# Power_Distribution.net
KiCad netlist of a schematic drawn in Altium Designer
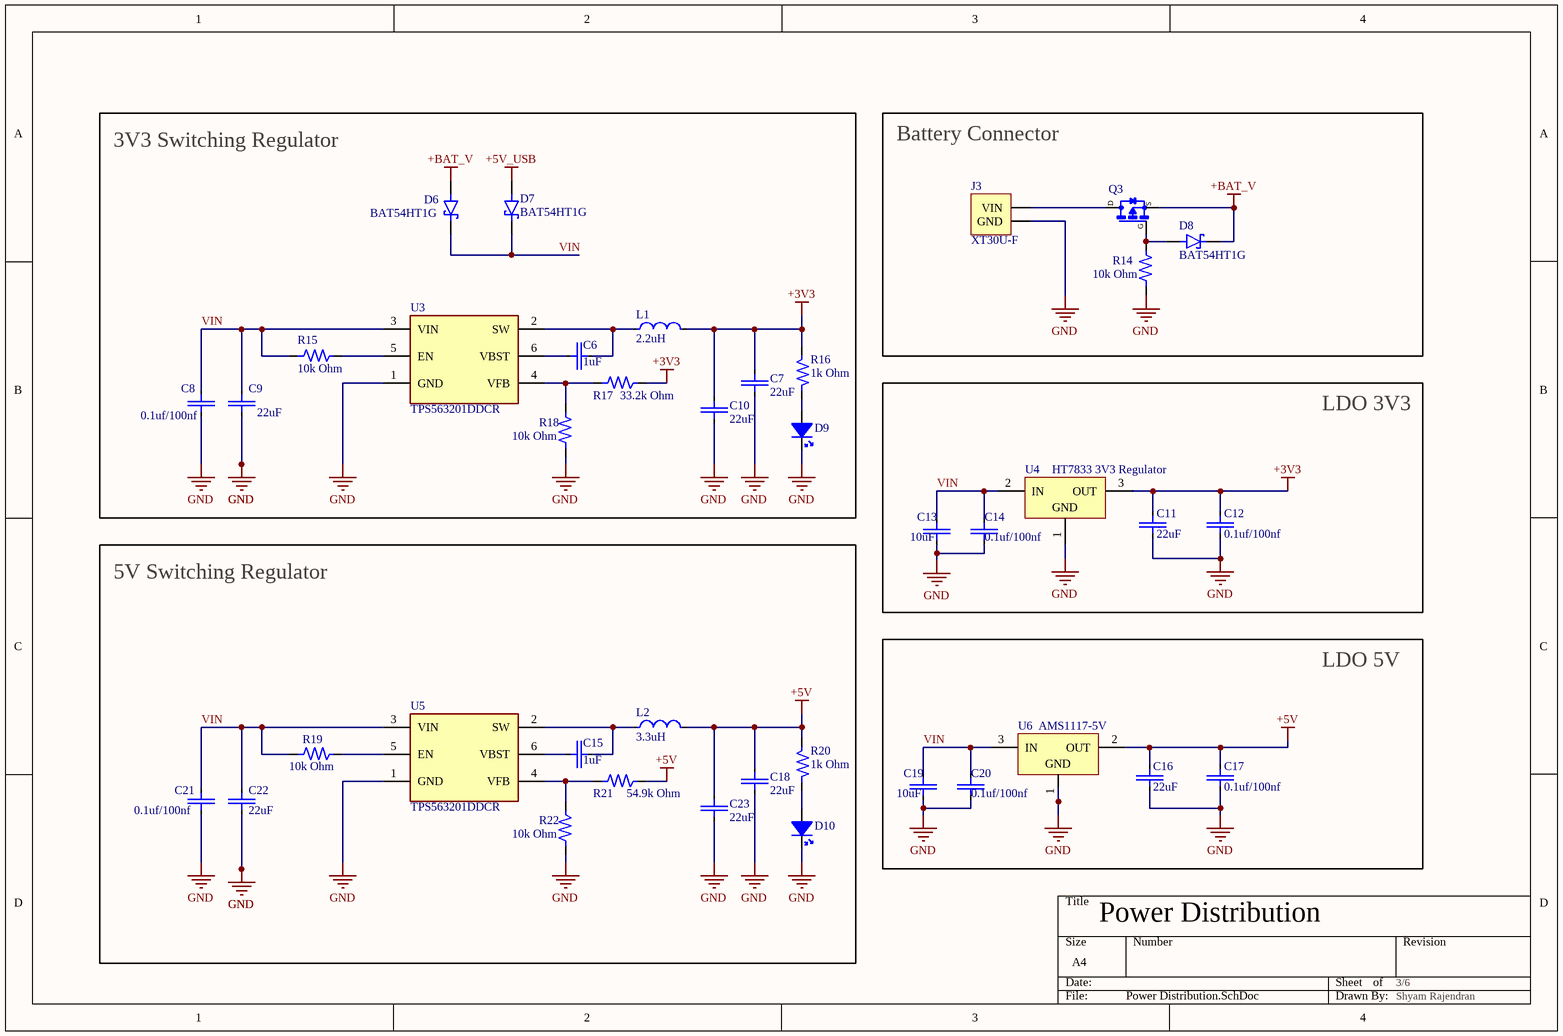
[diagram p0: Power Distribution.SchDoc]

(export (version "E")
  (design (tool "Eeschema 10.0.6"))
  (components
    (comp (ref "C6")
      (value "1uF")
      (footprint "10uf Capacitor")
      (fields
        (field (name "MANUFACTURER") "Yageo")
        (field (name "MANUFACTURER PART NUMBER") "CC0805KKX7R6BB105")
      )
      (libsource (lib "Sirius") (part "CC0805KKX7R6BB105"))
    )
    (comp (ref "C7")
      (value "22uF")
      (footprint "10uf Capacitor")
      (description "CL21A226KOQNNNE-Samsang-16V 22uF X5R ±10% 0805 Multilayer Ceramic Capacitors MLCC – SMD/SMT ROHS")
      (libsource (lib "Sirius") (part "22uF Capacitor"))
    )
    (comp (ref "C8")
      (value "0.1uf/100nf")
      (footprint "0.1uF Capacitor")
      (description "0.1 uF, Multilayer Ceramic Capacitor, 50 V, ï¿½ 10%, X7R, 0805 [2012 Metric]")
      (fields
        (field (name "MANUFACTURER") "Yageo")
        (field (name "MANUFACTURER PART NUMBER") "CC0805KRX7R9BB104")
      )
      (libsource (lib "Sirius") (part "CC0805KRX7R9BB104"))
    )
    (comp (ref "C9")
      (value "22uF")
      (footprint "10uf Capacitor")
      (description "CL21A226KOQNNNE-Samsang-16V 22uF X5R ±10% 0805 Multilayer Ceramic Capacitors MLCC – SMD/SMT ROHS")
      (libsource (lib "Sirius") (part "22uF Capacitor"))
    )
    (comp (ref "C10")
      (value "22uF")
      (footprint "10uf Capacitor")
      (description "CL21A226KOQNNNE-Samsang-16V 22uF X5R ±10% 0805 Multilayer Ceramic Capacitors MLCC – SMD/SMT ROHS")
      (libsource (lib "Sirius") (part "22uF Capacitor"))
    )
    (comp (ref "C11")
      (value "22uF")
      (footprint "10uf Capacitor")
      (description "CL21A226KOQNNNE-Samsang-16V 22uF X5R ±10% 0805 Multilayer Ceramic Capacitors MLCC – SMD/SMT ROHS")
      (libsource (lib "Sirius") (part "22uF Capacitor"))
    )
    (comp (ref "C12")
      (value "0.1uf/100nf")
      (footprint "0.1uF Capacitor")
      (description "0.1 uF, Multilayer Ceramic Capacitor, 50 V, ï¿½ 10%, X7R, 0805 [2012 Metric]")
      (fields
        (field (name "MANUFACTURER") "Yageo")
        (field (name "MANUFACTURER PART NUMBER") "CC0805KRX7R9BB104")
      )
      (libsource (lib "Sirius") (part "CC0805KRX7R9BB104"))
    )
    (comp (ref "C13")
      (value "10uF")
      (footprint "10uf Capacitor")
      (description "10uF, Multilayer Ceramic Capacitor, 25 V, ï¿½ 10%, X5R, 0805 [2012 Metric]")
      (fields
        (field (name "MANUFACTURER") "Murata")
        (field (name "MANUFACTURER PART NUMBER") "GRM21BR61E106KA73L")
      )
      (libsource (lib "Sirius") (part "GRM21BR61E106KA73L"))
    )
    (comp (ref "C14")
      (value "0.1uf/100nf")
      (footprint "0.1uF Capacitor")
      (description "0.1 uF, Multilayer Ceramic Capacitor, 50 V, ï¿½ 10%, X7R, 0805 [2012 Metric]")
      (fields
        (field (name "MANUFACTURER") "Yageo")
        (field (name "MANUFACTURER PART NUMBER") "CC0805KRX7R9BB104")
      )
      (libsource (lib "Sirius") (part "CC0805KRX7R9BB104"))
    )
    (comp (ref "C15")
      (value "1uF")
      (footprint "10uf Capacitor")
      (fields
        (field (name "MANUFACTURER") "Yageo")
        (field (name "MANUFACTURER PART NUMBER") "CC0805KKX7R6BB105")
      )
      (libsource (lib "Sirius") (part "CC0805KKX7R6BB105"))
    )
    (comp (ref "C16")
      (value "22uF")
      (footprint "10uf Capacitor")
      (description "CL21A226KOQNNNE-Samsang-16V 22uF X5R ±10% 0805 Multilayer Ceramic Capacitors MLCC – SMD/SMT ROHS")
      (libsource (lib "Sirius") (part "22uF Capacitor"))
    )
    (comp (ref "C17")
      (value "0.1uf/100nf")
      (footprint "0.1uF Capacitor")
      (description "0.1 uF, Multilayer Ceramic Capacitor, 50 V, ï¿½ 10%, X7R, 0805 [2012 Metric]")
      (fields
        (field (name "MANUFACTURER") "Yageo")
        (field (name "MANUFACTURER PART NUMBER") "CC0805KRX7R9BB104")
      )
      (libsource (lib "Sirius") (part "CC0805KRX7R9BB104"))
    )
    (comp (ref "C18")
      (value "22uF")
      (footprint "10uf Capacitor")
      (description "CL21A226KOQNNNE-Samsang-16V 22uF X5R ±10% 0805 Multilayer Ceramic Capacitors MLCC – SMD/SMT ROHS")
      (libsource (lib "Sirius") (part "22uF Capacitor"))
    )
    (comp (ref "C19")
      (value "10uF")
      (footprint "10uf Capacitor")
      (description "10uF, Multilayer Ceramic Capacitor, 25 V, ï¿½ 10%, X5R, 0805 [2012 Metric]")
      (fields
        (field (name "MANUFACTURER") "Murata")
        (field (name "MANUFACTURER PART NUMBER") "GRM21BR61E106KA73L")
      )
      (libsource (lib "Sirius") (part "GRM21BR61E106KA73L"))
    )
    (comp (ref "C20")
      (value "0.1uf/100nf")
      (footprint "0.1uF Capacitor")
      (description "0.1 uF, Multilayer Ceramic Capacitor, 50 V, ï¿½ 10%, X7R, 0805 [2012 Metric]")
      (fields
        (field (name "MANUFACTURER") "Yageo")
        (field (name "MANUFACTURER PART NUMBER") "CC0805KRX7R9BB104")
      )
      (libsource (lib "Sirius") (part "CC0805KRX7R9BB104"))
    )
    (comp (ref "C21")
      (value "0.1uf/100nf")
      (footprint "0.1uF Capacitor")
      (description "0.1 uF, Multilayer Ceramic Capacitor, 50 V, ï¿½ 10%, X7R, 0805 [2012 Metric]")
      (fields
        (field (name "MANUFACTURER") "Yageo")
        (field (name "MANUFACTURER PART NUMBER") "CC0805KRX7R9BB104")
      )
      (libsource (lib "Sirius") (part "CC0805KRX7R9BB104"))
    )
    (comp (ref "C22")
      (value "22uF")
      (footprint "10uf Capacitor")
      (description "CL21A226KOQNNNE-Samsang-16V 22uF X5R ±10% 0805 Multilayer Ceramic Capacitors MLCC – SMD/SMT ROHS")
      (libsource (lib "Sirius") (part "22uF Capacitor"))
    )
    (comp (ref "C23")
      (value "22uF")
      (footprint "10uf Capacitor")
      (description "CL21A226KOQNNNE-Samsang-16V 22uF X5R ±10% 0805 Multilayer Ceramic Capacitors MLCC – SMD/SMT ROHS")
      (libsource (lib "Sirius") (part "22uF Capacitor"))
    )
    (comp (ref "D6")
      (value "BAT54HT1G")
      (footprint "SOD2513X110N")
      (fields (field (name "MF") "Infineon Technologies") (field (name "MP") "BAS3010A03WE6327HTSA1"))
      (libsource (lib "Sirius") (part "BAT54HT1G"))
    )
    (comp (ref "D7")
      (value "BAT54HT1G")
      (footprint "SOD2513X110N")
      (fields (field (name "MF") "Infineon Technologies") (field (name "MP") "BAS3010A03WE6327HTSA1"))
      (libsource (lib "Sirius") (part "BAT54HT1G"))
    )
    (comp (ref "D8")
      (value "BAT54HT1G")
      (footprint "SOD2513X110N")
      (fields (field (name "MF") "Infineon Technologies") (field (name "MP") "BAS3010A03WE6327HTSA1"))
      (libsource (lib "Sirius") (part "BAT54HT1G"))
    )
    (comp (ref "D9") (value "RED, 0805") (footprint "led red") (libsource (lib "Sirius") (part "LED RED")))
    (comp (ref "D10") (value "RED, 0805") (footprint "led red") (libsource (lib "Sirius") (part "LED RED")))
    (comp (ref "J3")
      (value "XT30U-F")
      (footprint "XT30UPB-F")
      (libsource (lib "Sirius") (part "XT30 Connector"))
    )
    (comp (ref "L1")
      (value "2.2uH")
      (footprint "SWPA4030S")
      (description "SWPA4030S2R2MT-Sunlord-2.2uH 2.95A 20% 39mOhm Shielded Wirewound Power Inductor SMD")
      (fields (field (name "TOLERANCE") "20%"))
      (libsource (lib "Sirius") (part "2.2uH Inductor"))
    )
    (comp (ref "L2")
      (value "3.3uH")
      (footprint "SWPA5020")
      (description "SWPA5020S3R3MT-Sunlord-3.3uH 2.5A 20% 56mOhm Shielded Wirewound Power Inductor SMD")
      (fields (field (name "TOLERANCE") "20%"))
      (libsource (lib "Sirius") (part "3.3uH Inductor"))
    )
    (comp (ref "Q3")
      (value "SL2P10A")
      (footprint "P Mosfet SL2P10A")
      (fields (field (name "MF") "Vishay Siliconix") (field (name "MP") "SI2323DS-T1-E3"))
      (libsource (lib "Sirius") (part "SL2P10A"))
    )
    (comp (ref "R14")
      (value "10k Ohm")
      (footprint "RESC2013X60X35ML10T20")
      (description "10 kOhm, SMD Chip Resistor, ï¿½ 1%, 125 mW, 0805 [2012 Metric], Thick Film, General Purpose")
      (fields
        (field (name "MANUFACTURER") "Yageo")
        (field (name "MANUFACTURER PART NUMBER") "RC0805FR-0710KL")
      )
      (libsource (lib "Sirius") (part "RC0805FR-0710KL"))
    )
    (comp (ref "R15")
      (value "10k Ohm")
      (footprint "RESC2013X60X35ML10T20")
      (description "10 kOhm, SMD Chip Resistor, ï¿½ 1%, 125 mW, 0805 [2012 Metric], Thick Film, General Purpose")
      (fields
        (field (name "MANUFACTURER") "Yageo")
        (field (name "MANUFACTURER PART NUMBER") "RC0805FR-0710KL")
      )
      (libsource (lib "Sirius") (part "RC0805FR-0710KL"))
    )
    (comp (ref "R16")
      (value "1k Ohm")
      (footprint "1k 0805 Resistor")
      (description "1k Ohm, 0805, SMD Chip Resistor , ï¿½ 1%, 125 mW,[2012 Metric], Thick Film, General Purpose")
      (fields
        (field (name "MANUFACTURER") "Yageo")
        (field (name "MANUFACTURER PART NUMBER") "RC0805FR-071KL")
      )
      (libsource (lib "Sirius") (part "RC0805FR-071KL"))
    )
    (comp (ref "R17")
      (value "33.2k Ohm")
      (footprint "1k 0805 Resistor")
      (description "0805")
      (libsource (lib "Sirius") (part "33.2k Ohm"))
    )
    (comp (ref "R18")
      (value "10k Ohm")
      (footprint "RESC2013X60X35ML10T20")
      (description "10 kOhm, SMD Chip Resistor, ï¿½ 1%, 125 mW, 0805 [2012 Metric], Thick Film, General Purpose")
      (fields
        (field (name "MANUFACTURER") "Yageo")
        (field (name "MANUFACTURER PART NUMBER") "RC0805FR-0710KL")
      )
      (libsource (lib "Sirius") (part "RC0805FR-0710KL"))
    )
    (comp (ref "R19")
      (value "10k Ohm")
      (footprint "RESC2013X60X35ML10T20")
      (description "10 kOhm, SMD Chip Resistor, ï¿½ 1%, 125 mW, 0805 [2012 Metric], Thick Film, General Purpose")
      (fields
        (field (name "MANUFACTURER") "Yageo")
        (field (name "MANUFACTURER PART NUMBER") "RC0805FR-0710KL")
      )
      (libsource (lib "Sirius") (part "RC0805FR-0710KL"))
    )
    (comp (ref "R20")
      (value "1k Ohm")
      (footprint "1k 0805 Resistor")
      (description "1k Ohm, 0805, SMD Chip Resistor , ï¿½ 1%, 125 mW,[2012 Metric], Thick Film, General Purpose")
      (fields
        (field (name "MANUFACTURER") "Yageo")
        (field (name "MANUFACTURER PART NUMBER") "RC0805FR-071KL")
      )
      (libsource (lib "Sirius") (part "RC0805FR-071KL"))
    )
    (comp (ref "R21")
      (value "54.9k Ohm")
      (footprint "1k 0805 Resistor")
      (description "0805")
      (libsource (lib "Sirius") (part "54.9k Ohm"))
    )
    (comp (ref "R22")
      (value "10k Ohm")
      (footprint "RESC2013X60X35ML10T20")
      (description "10 kOhm, SMD Chip Resistor, ï¿½ 1%, 125 mW, 0805 [2012 Metric], Thick Film, General Purpose")
      (fields
        (field (name "MANUFACTURER") "Yageo")
        (field (name "MANUFACTURER PART NUMBER") "RC0805FR-0710KL")
      )
      (libsource (lib "Sirius") (part "RC0805FR-0710KL"))
    )
    (comp (ref "U3")
      (value "TPS563201DDCR")
      (footprint "TPS563201DDCR")
      (description "4.5 V to 17 V input, 3 A output, synchronous step-down converter in Eco-mode")
      (fields (field (name "MF") "Texas Instruments"))
      (libsource (lib "Sirius") (part "TPS563201DDCR"))
    )
    (comp (ref "U4")
      (value "HT7833 3V3 Regulator")
      (footprint "HT7833")
      (description "3V3 Voltage Regulator")
      (libsource (lib "Sirius") (part "HT7833"))
    )
    (comp (ref "U5")
      (value "TPS563201DDCR")
      (footprint "TPS563201DDCR")
      (description "4.5 V to 17 V input, 3 A output, synchronous step-down converter in Eco-mode")
      (fields (field (name "MF") "Texas Instruments"))
      (libsource (lib "Sirius") (part "TPS563201DDCR"))
    )
    (comp (ref "U6")
      (value "AMS1117-5V")
      (footprint "AMS1117, 5V")
      (description "SOT89")
      (libsource (lib "Sirius") (part "AMS1117-5V"))
    )
  )
  (nets
    (net (code "1") (name "+3V3") (class "Default")
      (node (ref "C10") (pin "2") (pinfunction "2_2") (pintype "passive"))
      (node (ref "C11") (pin "2") (pinfunction "2_2") (pintype "passive"))
      (node (ref "C12") (pin "2") (pinfunction "2_2") (pintype "passive"))
      (node (ref "C7") (pin "2") (pinfunction "2_2") (pintype "passive"))
      (node (ref "L1") (pin "2") (pinfunction "2_2") (pintype "passive"))
      (node (ref "R16") (pin "2") (pinfunction "2_2") (pintype "passive"))
      (node (ref "R17") (pin "2") (pinfunction "2_2") (pintype "passive"))
      (node (ref "U4") (pin "3") (pinfunction "OUT_3") (pintype "power_in"))
    )
    (net (code "2") (name "+5V") (class "Default")
      (node (ref "C16") (pin "2") (pinfunction "2_2") (pintype "passive"))
      (node (ref "C17") (pin "2") (pinfunction "2_2") (pintype "passive"))
      (node (ref "C18") (pin "2") (pinfunction "2_2") (pintype "passive"))
      (node (ref "C23") (pin "2") (pinfunction "2_2") (pintype "passive"))
      (node (ref "L2") (pin "2") (pinfunction "2_2") (pintype "passive"))
      (node (ref "R20") (pin "2") (pinfunction "2_2") (pintype "passive"))
      (node (ref "R21") (pin "2") (pinfunction "2_2") (pintype "passive"))
      (node (ref "U6") (pin "2") (pinfunction "OUT_2") (pintype "power_in"))
    )
    (net (code "3") (name "+5V_USB") (class "Default")
      (node (ref "D7") (pin "A") (pinfunction "A_A") (pintype "passive"))
    )
    (net (code "4") (name "+BAT_V") (class "Default")
      (node (ref "D6") (pin "A") (pinfunction "A_A") (pintype "passive"))
      (node (ref "D8") (pin "C") (pinfunction "K_C") (pintype "passive"))
      (node (ref "Q3") (pin "S") (pinfunction "S_S") (pintype "passive"))
    )
    (net (code "5") (name "/VIN") (class "Default")
      (node (ref "C13") (pin "2") (pinfunction "2_2") (pintype "passive"))
      (node (ref "C14") (pin "2") (pinfunction "2_2") (pintype "passive"))
      (node (ref "C19") (pin "2") (pinfunction "2_2") (pintype "passive"))
      (node (ref "C20") (pin "2") (pinfunction "2_2") (pintype "passive"))
      (node (ref "C21") (pin "2") (pinfunction "2_2") (pintype "passive"))
      (node (ref "C22") (pin "2") (pinfunction "2_2") (pintype "passive"))
      (node (ref "C8") (pin "2") (pinfunction "2_2") (pintype "passive"))
      (node (ref "C9") (pin "2") (pinfunction "2_2") (pintype "passive"))
      (node (ref "D6") (pin "C") (pinfunction "K_C") (pintype "passive"))
      (node (ref "D7") (pin "C") (pinfunction "K_C") (pintype "passive"))
      (node (ref "R15") (pin "1") (pinfunction "1_1") (pintype "passive"))
      (node (ref "R19") (pin "1") (pinfunction "1_1") (pintype "passive"))
      (node (ref "U3") (pin "3") (pinfunction "VIN_3") (pintype "passive"))
      (node (ref "U4") (pin "2") (pinfunction "IN_2") (pintype "power_in"))
      (node (ref "U5") (pin "3") (pinfunction "VIN_3") (pintype "passive"))
      (node (ref "U6") (pin "3") (pinfunction "IN_3") (pintype "power_in"))
    )
    (net (code "6") (name "GND") (class "Default")
      (node (ref "C10") (pin "1") (pinfunction "1_1") (pintype "passive"))
      (node (ref "C11") (pin "1") (pinfunction "1_1") (pintype "passive"))
      (node (ref "C12") (pin "1") (pinfunction "1_1") (pintype "passive"))
      (node (ref "C13") (pin "1") (pinfunction "1_1") (pintype "passive"))
      (node (ref "C14") (pin "1") (pinfunction "1_1") (pintype "passive"))
      (node (ref "C16") (pin "1") (pinfunction "1_1") (pintype "passive"))
      (node (ref "C17") (pin "1") (pinfunction "1_1") (pintype "passive"))
      (node (ref "C18") (pin "1") (pinfunction "1_1") (pintype "passive"))
      (node (ref "C19") (pin "1") (pinfunction "1_1") (pintype "passive"))
      (node (ref "C20") (pin "1") (pinfunction "1_1") (pintype "passive"))
      (node (ref "C21") (pin "1") (pinfunction "1_1") (pintype "passive"))
      (node (ref "C22") (pin "1") (pinfunction "1_1") (pintype "passive"))
      (node (ref "C23") (pin "1") (pinfunction "1_1") (pintype "passive"))
      (node (ref "C7") (pin "1") (pinfunction "1_1") (pintype "passive"))
      (node (ref "C8") (pin "1") (pinfunction "1_1") (pintype "passive"))
      (node (ref "C9") (pin "1") (pinfunction "1_1") (pintype "passive"))
      (node (ref "D10") (pin "C") (pinfunction "2_C") (pintype "passive"))
      (node (ref "D9") (pin "C") (pinfunction "2_C") (pintype "passive"))
      (node (ref "J3") (pin "GND") (pinfunction "GND_GND") (pintype "passive"))
      (node (ref "R14") (pin "1") (pinfunction "1_1") (pintype "passive"))
      (node (ref "R18") (pin "1") (pinfunction "1_1") (pintype "passive"))
      (node (ref "R22") (pin "1") (pinfunction "1_1") (pintype "passive"))
      (node (ref "U3") (pin "1") (pinfunction "GND_1") (pintype "passive"))
      (node (ref "U4") (pin "1") (pinfunction "GND_1") (pintype "power_in"))
      (node (ref "U5") (pin "1") (pinfunction "GND_1") (pintype "passive"))
      (node (ref "U6") (pin "1") (pinfunction "GND_1") (pintype "power_in"))
    )
    (net (code "7") (name "Net-(D8-PadA)") (class "Default")
      (node (ref "D8") (pin "A") (pinfunction "A_A") (pintype "passive"))
      (node (ref "Q3") (pin "G") (pinfunction "G_G") (pintype "passive"))
      (node (ref "R14") (pin "2") (pinfunction "2_2") (pintype "passive"))
    )
    (net (code "8") (name "Net-(D9-1)") (class "Default")
      (node (ref "D9") (pin "A") (pinfunction "1_A") (pintype "passive"))
      (node (ref "R16") (pin "1") (pinfunction "1_1") (pintype "passive"))
    )
    (net (code "9") (name "Net-(D10-1)") (class "Default")
      (node (ref "D10") (pin "A") (pinfunction "1_A") (pintype "passive"))
      (node (ref "R20") (pin "1") (pinfunction "1_1") (pintype "passive"))
    )
    (net (code "10") (name "Net-(J3-PadVIN)") (class "Default")
      (node (ref "J3") (pin "VIN") (pinfunction "VIN_VIN") (pintype "passive"))
      (node (ref "Q3") (pin "D") (pinfunction "D_D") (pintype "passive"))
    )
    (net (code "11") (name "Net-(U3-EN)") (class "Default")
      (node (ref "R15") (pin "2") (pinfunction "2_2") (pintype "passive"))
      (node (ref "U3") (pin "5") (pinfunction "EN_5") (pintype "passive"))
    )
    (net (code "12") (name "Net-(U3-SW)") (class "Default")
      (node (ref "C6") (pin "2") (pinfunction "2_2") (pintype "passive"))
      (node (ref "L1") (pin "1") (pinfunction "1_1") (pintype "passive"))
      (node (ref "U3") (pin "2") (pinfunction "SW_2") (pintype "passive"))
    )
    (net (code "13") (name "Net-(U3-VBST)") (class "Default")
      (node (ref "C6") (pin "1") (pinfunction "1_1") (pintype "passive"))
      (node (ref "U3") (pin "6") (pinfunction "VBST_6") (pintype "passive"))
    )
    (net (code "14") (name "Net-(U3-VFB)") (class "Default")
      (node (ref "R17") (pin "1") (pinfunction "1_1") (pintype "passive"))
      (node (ref "R18") (pin "2") (pinfunction "2_2") (pintype "passive"))
      (node (ref "U3") (pin "4") (pinfunction "VFB_4") (pintype "passive"))
    )
    (net (code "15") (name "Net-(U5-EN)") (class "Default")
      (node (ref "R19") (pin "2") (pinfunction "2_2") (pintype "passive"))
      (node (ref "U5") (pin "5") (pinfunction "EN_5") (pintype "passive"))
    )
    (net (code "16") (name "Net-(U5-SW)") (class "Default")
      (node (ref "C15") (pin "2") (pinfunction "2_2") (pintype "passive"))
      (node (ref "L2") (pin "1") (pinfunction "1_1") (pintype "passive"))
      (node (ref "U5") (pin "2") (pinfunction "SW_2") (pintype "passive"))
    )
    (net (code "17") (name "Net-(U5-VBST)") (class "Default")
      (node (ref "C15") (pin "1") (pinfunction "1_1") (pintype "passive"))
      (node (ref "U5") (pin "6") (pinfunction "VBST_6") (pintype "passive"))
    )
    (net (code "18") (name "Net-(U5-VFB)") (class "Default")
      (node (ref "R21") (pin "1") (pinfunction "1_1") (pintype "passive"))
      (node (ref "R22") (pin "2") (pinfunction "2_2") (pintype "passive"))
      (node (ref "U5") (pin "4") (pinfunction "VFB_4") (pintype "passive"))
    )
  )
)
